# FubarinoMini_v14.net
KiCad netlist of a schematic drawn in EAGLE
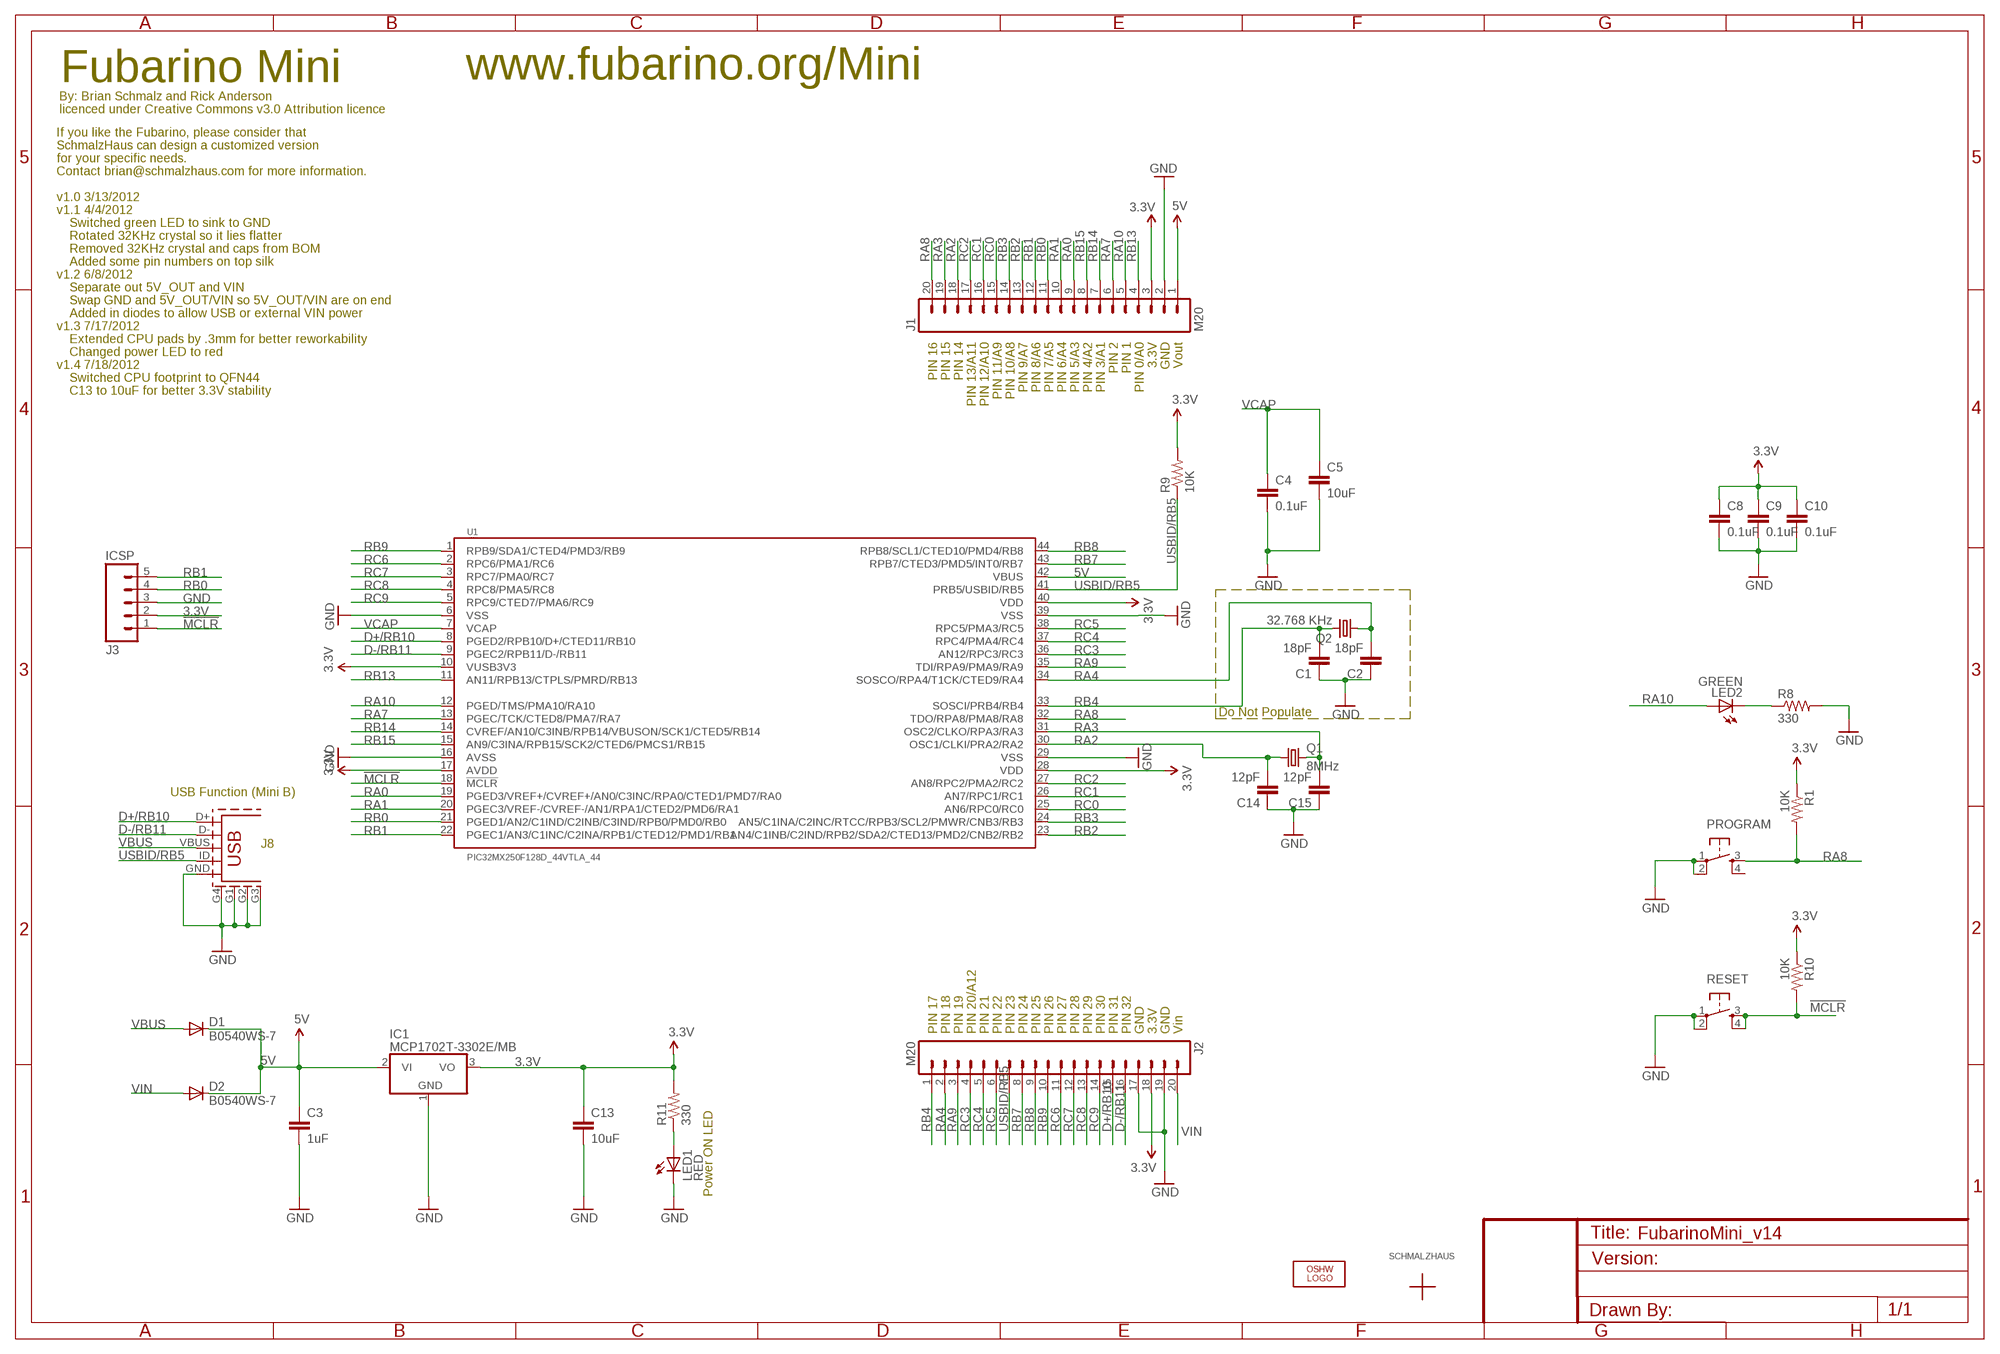
[diagram p0: schematic, sheet 1]

(export (version "E")
  (design (tool "Eeschema 10.0.6"))
  (components
    (comp (ref "C1")
      (value "18pF")
      (footprint "eagle-import:0603-CAP")
      (libsource (lib "eagle-import") (part "SparkFun_CAP0603-CAP"))
    )
    (comp (ref "C2")
      (value "18pF")
      (footprint "eagle-import:0603-CAP")
      (libsource (lib "eagle-import") (part "SparkFun_CAP0603-CAP"))
    )
    (comp (ref "C3")
      (value "1uF")
      (footprint "eagle-import:0603-CAP")
      (libsource (lib "eagle-import") (part "SparkFun_CAP0603-CAP"))
    )
    (comp (ref "C4")
      (value "0.1uF")
      (footprint "eagle-import:0603-CAP")
      (libsource (lib "eagle-import") (part "SparkFun_CAP0603-CAP"))
    )
    (comp (ref "C5")
      (value "10uF")
      (footprint "eagle-import:0805")
      (libsource (lib "eagle-import") (part "CAP0805"))
    )
    (comp (ref "C8")
      (value "0.1uF")
      (footprint "eagle-import:0603-CAP")
      (libsource (lib "eagle-import") (part "SparkFun_CAP0603-CAP"))
    )
    (comp (ref "C9")
      (value "0.1uF")
      (footprint "eagle-import:0603-CAP")
      (libsource (lib "eagle-import") (part "SparkFun_CAP0603-CAP"))
    )
    (comp (ref "C10")
      (value "0.1uF")
      (footprint "eagle-import:0603")
      (libsource (lib "eagle-import") (part "CAP0603"))
    )
    (comp (ref "C13")
      (value "10uF")
      (footprint "eagle-import:0805")
      (libsource (lib "eagle-import") (part "SparkFun02-20-08_CAP0805"))
    )
    (comp (ref "C14")
      (value "12pF")
      (footprint "eagle-import:0603-CAP")
      (libsource (lib "eagle-import") (part "SparkFun_CAP0603-CAP"))
    )
    (comp (ref "C15")
      (value "12pF")
      (footprint "eagle-import:0603-CAP")
      (libsource (lib "eagle-import") (part "SparkFun_CAP0603-CAP"))
    )
    (comp (ref "D1")
      (value "B0540WS-7")
      (footprint "eagle-import:SOD-323")
      (libsource (lib "eagle-import") (part "DIODESOD"))
    )
    (comp (ref "D2")
      (value "B0540WS-7")
      (footprint "eagle-import:SOD-323")
      (libsource (lib "eagle-import") (part "DIODESOD"))
    )
    (comp (ref "IC1")
      (value "MCP1702T-3302E/MB")
      (footprint "eagle-import:SOT89")
      (libsource (lib "eagle-import") (part "MCP1703MB33"))
    )
    (comp (ref "ICSP")
      (value "J3")
      (footprint "eagle-import:1X05_NOSILK")
      (libsource (lib "eagle-import") (part "M05NOSLILK"))
    )
    (comp (ref "J1")
      (value "M20")
      (footprint "eagle-import:1X20_NO_PIN1")
      (libsource (lib "eagle-import") (part "M20"))
    )
    (comp (ref "J2")
      (value "M20")
      (footprint "eagle-import:1X20_NO_PIN1")
      (libsource (lib "eagle-import") (part "M20"))
    )
    (comp (ref "J8")
      (value "USB_5PIN")
      (footprint "eagle-import:USB-MINIB")
      (libsource (lib "eagle-import") (part "USB_5PIN"))
    )
    (comp (ref "LED1")
      (value "RED")
      (footprint "eagle-import:LED-0603")
      (libsource (lib "eagle-import") (part "LED0603"))
    )
    (comp (ref "LED2")
      (value "GREEN")
      (footprint "eagle-import:LED-0603")
      (libsource (lib "eagle-import") (part "LED0603"))
    )
    (comp (ref "LOGO1")
      (value "OSHW_LOGO_8MILX0070-NT")
      (footprint "eagle-import:OSHW_8X70_NOTEXT")
      (libsource (lib "eagle-import") (part "OSHW_LOGO_8MILX0070-NT"))
    )
    (comp (ref "PROGRAM")
      (value "TAC_SWITCHSND")
      (footprint "eagle-import:TACTILE_SWITCH_SMD")
      (libsource (lib "eagle-import") (part "TAC_SWITCHSND"))
    )
    (comp (ref "Q1")
      (value "8MHz")
      (footprint "eagle-import:NX5032_5MM_3.2MM_CRYSTAL")
      (libsource (lib "eagle-import") (part "CRYSTALNX5032"))
    )
    (comp (ref "Q2")
      (value "32.768 KHz")
      (footprint "eagle-import:TC26H")
      (libsource (lib "eagle-import") (part "CRYSTALTC26H"))
    )
    (comp (ref "R1")
      (value "10K")
      (footprint "eagle-import:0603-RES")
      (libsource (lib "eagle-import") (part "RESISTOR0603-RES"))
    )
    (comp (ref "R8")
      (value "330")
      (footprint "eagle-import:0603-RES")
      (libsource (lib "eagle-import") (part "RESISTOR0603-RES"))
    )
    (comp (ref "R9")
      (value "10K")
      (footprint "eagle-import:0603-RES")
      (libsource (lib "eagle-import") (part "RESISTOR0603-RES"))
    )
    (comp (ref "R10")
      (value "10K")
      (footprint "eagle-import:0603-RES")
      (libsource (lib "eagle-import") (part "RESISTOR0603-RES"))
    )
    (comp (ref "R11")
      (value "330")
      (footprint "eagle-import:0603-RES")
      (libsource (lib "eagle-import") (part "RESISTOR0603-RES"))
    )
    (comp (ref "RESET")
      (value "TAC_SWITCHSND")
      (footprint "eagle-import:TACTILE_SWITCH_SMD")
      (libsource (lib "eagle-import") (part "TAC_SWITCHSND"))
    )
    (comp (ref "U$1")
      (value "SCHMALZHAUSSCHMALZHAUS_SMALL")
      (footprint "eagle-import:SCHMALZHAUS_SMALL")
      (libsource (lib "eagle-import") (part "SCHMALZHAUSSCHMALZHAUS_SMALL"))
    )
    (comp (ref "U1")
      (value "PIC32MX250F128D_44VTLA_44")
      (footprint "eagle-import:QFN-44-8X8-NOPAD")
      (libsource (lib "eagle-import") (part "PIC32MX2XX_44QFN44"))
    )
  )
  (nets
    (net (code "1") (name "/D+{slash}RB10") (class "Default")
      (node (ref "J2") (pin "15") (pinfunction "15_15") (pintype "passive"))
      (node (ref "J8") (pin "D+") (pinfunction "D+_D+") (pintype "bidirectional"))
      (node (ref "U1") (pin "8") (pinfunction "PGED2/RPB10/D+/CTED11/RB10_8") (pintype "bidirectional"))
    )
    (net (code "2") (name "/D-{slash}RB11") (class "Default")
      (node (ref "J2") (pin "16") (pinfunction "16_16") (pintype "passive"))
      (node (ref "J8") (pin "D-") (pinfunction "D-_D-") (pintype "bidirectional"))
      (node (ref "U1") (pin "9") (pinfunction "PGEC2/RPB11/D-/RB11_9") (pintype "bidirectional"))
    )
    (net (code "3") (name "/RA0") (class "Default")
      (node (ref "J1") (pin "9") (pinfunction "9_9") (pintype "passive"))
      (node (ref "U1") (pin "19") (pinfunction "PGED3/VREF+/CVREF+/AN0/C3INC/RPA0/CTED1/PMD7/RA0_19") (pintype "bidirectional"))
    )
    (net (code "4") (name "/RA1") (class "Default")
      (node (ref "J1") (pin "10") (pinfunction "10_10") (pintype "passive"))
      (node (ref "U1") (pin "20") (pinfunction "PGEC3/VREF-/CVREF-/AN1/RPA1/CTED2/PMD6/RA1_20") (pintype "bidirectional"))
    )
    (net (code "5") (name "/RA2") (class "Default")
      (node (ref "C14") (pin "2") (pinfunction "2_2") (pintype "passive"))
      (node (ref "J1") (pin "18") (pinfunction "18_18") (pintype "passive"))
      (node (ref "Q1") (pin "1") (pinfunction "1_1") (pintype "passive"))
      (node (ref "U1") (pin "30") (pinfunction "OSC1/CLKI/PRA2/RA2_30") (pintype "bidirectional"))
    )
    (net (code "6") (name "/RA3") (class "Default")
      (node (ref "C15") (pin "2") (pinfunction "2_2") (pintype "passive"))
      (node (ref "J1") (pin "19") (pinfunction "19_19") (pintype "passive"))
      (node (ref "Q1") (pin "2") (pinfunction "2_2") (pintype "passive"))
      (node (ref "U1") (pin "31") (pinfunction "OSC2/CLKO/RPA3/RA3_31") (pintype "bidirectional"))
    )
    (net (code "7") (name "/RA4") (class "Default")
      (node (ref "C2") (pin "2") (pinfunction "2_2") (pintype "passive"))
      (node (ref "J2") (pin "2") (pinfunction "2_2") (pintype "passive"))
      (node (ref "Q2") (pin "1") (pinfunction "1_1") (pintype "passive"))
      (node (ref "U1") (pin "34") (pinfunction "SOSCO/RPA4/T1CK/CTED9/RA4_34") (pintype "bidirectional"))
    )
    (net (code "8") (name "/RA7") (class "Default")
      (node (ref "J1") (pin "6") (pinfunction "6_6") (pintype "passive"))
      (node (ref "U1") (pin "13") (pinfunction "PGEC/TCK/CTED8/PMA7/RA7_13") (pintype "bidirectional"))
    )
    (net (code "9") (name "/RA8") (class "Default")
      (node (ref "J1") (pin "20") (pinfunction "20_20") (pintype "passive"))
      (node (ref "PROGRAM") (pin "3") (pinfunction "3_3") (pintype "passive"))
      (node (ref "R1") (pin "2") (pinfunction "2_2") (pintype "passive"))
      (node (ref "U1") (pin "32") (pinfunction "TDO/RPA8/PMA8/RA8_32") (pintype "bidirectional"))
    )
    (net (code "10") (name "/RA9") (class "Default")
      (node (ref "J2") (pin "3") (pinfunction "3_3") (pintype "passive"))
      (node (ref "U1") (pin "35") (pinfunction "TDI/RPA9/PMA9/RA9_35") (pintype "bidirectional"))
    )
    (net (code "11") (name "/RA10") (class "Default")
      (node (ref "J1") (pin "5") (pinfunction "5_5") (pintype "passive"))
      (node (ref "LED2") (pin "A") (pinfunction "A_A") (pintype "passive"))
      (node (ref "U1") (pin "12") (pinfunction "PGED/TMS/PMA10/RA10_12") (pintype "bidirectional"))
    )
    (net (code "12") (name "/RB0") (class "Default")
      (node (ref "ICSP") (pin "4") (pinfunction "4_4") (pintype "passive"))
      (node (ref "J1") (pin "11") (pinfunction "11_11") (pintype "passive"))
      (node (ref "U1") (pin "21") (pinfunction "PGED1/AN2/C1IND/C2INB/C3IND/RPB0/PMD0/RB0_21") (pintype "bidirectional"))
    )
    (net (code "13") (name "/RB1") (class "Default")
      (node (ref "ICSP") (pin "5") (pinfunction "5_5") (pintype "passive"))
      (node (ref "J1") (pin "12") (pinfunction "12_12") (pintype "passive"))
      (node (ref "U1") (pin "22") (pinfunction "PGEC1/AN3/C1INC/C2INA/RPB1/CTED12/PMD1/RB1_22") (pintype "bidirectional"))
    )
    (net (code "14") (name "/RB2") (class "Default")
      (node (ref "J1") (pin "13") (pinfunction "13_13") (pintype "passive"))
      (node (ref "U1") (pin "23") (pinfunction "AN4/C1INB/C2IND/RPB2/SDA2/CTED13/PMD2/CNB2/RB2_23") (pintype "bidirectional"))
    )
    (net (code "15") (name "/RB3") (class "Default")
      (node (ref "J1") (pin "14") (pinfunction "14_14") (pintype "passive"))
      (node (ref "U1") (pin "24") (pinfunction "AN5/C1INA/C2INC/RTCC/RPB3/SCL2/PMWR/CNB3/RB3_24") (pintype "bidirectional"))
    )
    (net (code "16") (name "/RB4") (class "Default")
      (node (ref "C1") (pin "2") (pinfunction "2_2") (pintype "passive"))
      (node (ref "J2") (pin "1") (pinfunction "1_1") (pintype "passive"))
      (node (ref "Q2") (pin "2") (pinfunction "2_2") (pintype "passive"))
      (node (ref "U1") (pin "33") (pinfunction "SOSCI/PRB4/RB4_33") (pintype "bidirectional"))
    )
    (net (code "17") (name "/RB7") (class "Default")
      (node (ref "J2") (pin "8") (pinfunction "8_8") (pintype "passive"))
      (node (ref "U1") (pin "43") (pinfunction "RPB7/CTED3/PMD5/INT0/RB7_43") (pintype "bidirectional"))
    )
    (net (code "18") (name "/RB8") (class "Default")
      (node (ref "J2") (pin "9") (pinfunction "9_9") (pintype "passive"))
      (node (ref "U1") (pin "44") (pinfunction "RPB8/SCL1/CTED10/PMD4/RB8_44") (pintype "bidirectional"))
    )
    (net (code "19") (name "/RB9") (class "Default")
      (node (ref "J2") (pin "10") (pinfunction "10_10") (pintype "passive"))
      (node (ref "U1") (pin "1") (pinfunction "RPB9/SDA1/CTED4/PMD3/RB9_1") (pintype "bidirectional"))
    )
    (net (code "20") (name "/RB13") (class "Default")
      (node (ref "J1") (pin "4") (pinfunction "4_4") (pintype "passive"))
      (node (ref "U1") (pin "11") (pinfunction "AN11/RPB13/CTPLS/PMRD/RB13_11") (pintype "bidirectional"))
    )
    (net (code "21") (name "/RB14") (class "Default")
      (node (ref "J1") (pin "7") (pinfunction "7_7") (pintype "passive"))
      (node (ref "U1") (pin "14") (pinfunction "CVREF/AN10/C3INB/RPB14/VBUSON/SCK1/CTED5/RB14_14") (pintype "bidirectional"))
    )
    (net (code "22") (name "/RB15") (class "Default")
      (node (ref "J1") (pin "8") (pinfunction "8_8") (pintype "passive"))
      (node (ref "U1") (pin "15") (pinfunction "AN9/C3INA/RPB15/SCK2/CTED6/PMCS1/RB15_15") (pintype "bidirectional"))
    )
    (net (code "23") (name "/RC0") (class "Default")
      (node (ref "J1") (pin "15") (pinfunction "15_15") (pintype "passive"))
      (node (ref "U1") (pin "25") (pinfunction "AN6/RPC0/RC0_25") (pintype "bidirectional"))
    )
    (net (code "24") (name "/RC1") (class "Default")
      (node (ref "J1") (pin "16") (pinfunction "16_16") (pintype "passive"))
      (node (ref "U1") (pin "26") (pinfunction "AN7/RPC1/RC1_26") (pintype "bidirectional"))
    )
    (net (code "25") (name "/RC2") (class "Default")
      (node (ref "J1") (pin "17") (pinfunction "17_17") (pintype "passive"))
      (node (ref "U1") (pin "27") (pinfunction "AN8/RPC2/PMA2/RC2_27") (pintype "bidirectional"))
    )
    (net (code "26") (name "/RC3") (class "Default")
      (node (ref "J2") (pin "4") (pinfunction "4_4") (pintype "passive"))
      (node (ref "U1") (pin "36") (pinfunction "AN12/RPC3/RC3_36") (pintype "bidirectional"))
    )
    (net (code "27") (name "/RC4") (class "Default")
      (node (ref "J2") (pin "5") (pinfunction "5_5") (pintype "passive"))
      (node (ref "U1") (pin "37") (pinfunction "RPC4/PMA4/RC4_37") (pintype "bidirectional"))
    )
    (net (code "28") (name "/RC5") (class "Default")
      (node (ref "J2") (pin "6") (pinfunction "6_6") (pintype "passive"))
      (node (ref "U1") (pin "38") (pinfunction "RPC5/PMA3/RC5_38") (pintype "bidirectional"))
    )
    (net (code "29") (name "/RC6") (class "Default")
      (node (ref "J2") (pin "11") (pinfunction "11_11") (pintype "passive"))
      (node (ref "U1") (pin "2") (pinfunction "RPC6/PMA1/RC6_2") (pintype "bidirectional"))
    )
    (net (code "30") (name "/RC7") (class "Default")
      (node (ref "J2") (pin "12") (pinfunction "12_12") (pintype "passive"))
      (node (ref "U1") (pin "3") (pinfunction "RPC7/PMA0/RC7_3") (pintype "bidirectional"))
    )
    (net (code "31") (name "/RC8") (class "Default")
      (node (ref "J2") (pin "13") (pinfunction "13_13") (pintype "passive"))
      (node (ref "U1") (pin "4") (pinfunction "RPC8/PMA5/RC8_4") (pintype "bidirectional"))
    )
    (net (code "32") (name "/RC9") (class "Default")
      (node (ref "J2") (pin "14") (pinfunction "14_14") (pintype "passive"))
      (node (ref "U1") (pin "5") (pinfunction "RPC9/CTED7/PMA6/RC9_5") (pintype "bidirectional"))
    )
    (net (code "33") (name "/USBID{slash}RB5") (class "Default")
      (node (ref "J2") (pin "7") (pinfunction "7_7") (pintype "passive"))
      (node (ref "J8") (pin "ID") (pinfunction "USB_ID_ID") (pintype "bidirectional"))
      (node (ref "R9") (pin "1") (pinfunction "1_1") (pintype "passive"))
      (node (ref "U1") (pin "41") (pinfunction "PRB5/USBID/RB5_41") (pintype "bidirectional"))
    )
    (net (code "34") (name "/VBUS") (class "Default")
      (node (ref "D1") (pin "2") (pinfunction "A_2") (pintype "passive"))
      (node (ref "J8") (pin "VBUS") (pinfunction "VBUS_VBUS") (pintype "bidirectional"))
    )
    (net (code "35") (name "/VCAP") (class "Default")
      (node (ref "C4") (pin "1") (pinfunction "1_1") (pintype "passive"))
      (node (ref "C5") (pin "1") (pinfunction "1_1") (pintype "passive"))
      (node (ref "U1") (pin "7") (pinfunction "VCAP_7") (pintype "bidirectional"))
    )
    (net (code "36") (name "/VIN") (class "Default")
      (node (ref "D2") (pin "2") (pinfunction "A_2") (pintype "passive"))
      (node (ref "J2") (pin "20") (pinfunction "20_20") (pintype "passive"))
    )
    (net (code "37") (name "/~{MCLR}") (class "Default")
      (node (ref "ICSP") (pin "1") (pinfunction "1_1") (pintype "passive"))
      (node (ref "R10") (pin "2") (pinfunction "2_2") (pintype "passive"))
      (node (ref "RESET") (pin "3") (pinfunction "3_3") (pintype "passive"))
      (node (ref "RESET") (pin "4") (pinfunction "4_4") (pintype "passive"))
      (node (ref "U1") (pin "18") (pinfunction "~{MCLR}_18") (pintype "bidirectional"))
    )
    (net (code "38") (name "3.3V") (class "Default")
      (node (ref "C10") (pin "1") (pinfunction "1_1") (pintype "passive"))
      (node (ref "C13") (pin "1") (pinfunction "1_1") (pintype "passive"))
      (node (ref "C8") (pin "1") (pinfunction "1_1") (pintype "passive"))
      (node (ref "C9") (pin "1") (pinfunction "1_1") (pintype "passive"))
      (node (ref "IC1") (pin "3") (pinfunction "VO_3") (pintype "passive"))
      (node (ref "ICSP") (pin "2") (pinfunction "2_2") (pintype "passive"))
      (node (ref "J1") (pin "3") (pinfunction "3_3") (pintype "passive"))
      (node (ref "J2") (pin "18") (pinfunction "18_18") (pintype "passive"))
      (node (ref "R1") (pin "1") (pinfunction "1_1") (pintype "passive"))
      (node (ref "R10") (pin "1") (pinfunction "1_1") (pintype "passive"))
      (node (ref "R11") (pin "2") (pinfunction "2_2") (pintype "passive"))
      (node (ref "R9") (pin "2") (pinfunction "2_2") (pintype "passive"))
      (node (ref "U1") (pin "10") (pinfunction "VUSB3V3_10") (pintype "bidirectional"))
      (node (ref "U1") (pin "17") (pinfunction "AVDD_17") (pintype "bidirectional"))
      (node (ref "U1") (pin "28") (pinfunction "VDD_28") (pintype "bidirectional"))
      (node (ref "U1") (pin "40") (pinfunction "VDD_40") (pintype "bidirectional"))
    )
    (net (code "39") (name "5V") (class "Default")
      (node (ref "C3") (pin "1") (pinfunction "1_1") (pintype "passive"))
      (node (ref "D1") (pin "1") (pinfunction "C_1") (pintype "passive"))
      (node (ref "D2") (pin "1") (pinfunction "C_1") (pintype "passive"))
      (node (ref "IC1") (pin "2") (pinfunction "VI_2") (pintype "input"))
      (node (ref "IC1") (pin "2@1") (pinfunction "VI1_2@1") (pintype "input"))
      (node (ref "J1") (pin "1") (pinfunction "1_1") (pintype "passive"))
      (node (ref "U1") (pin "42") (pinfunction "VBUS_42") (pintype "bidirectional"))
    )
    (net (code "40") (name "GND") (class "Default")
      (node (ref "C1") (pin "1") (pinfunction "1_1") (pintype "passive"))
      (node (ref "C10") (pin "2") (pinfunction "2_2") (pintype "passive"))
      (node (ref "C13") (pin "2") (pinfunction "2_2") (pintype "passive"))
      (node (ref "C14") (pin "1") (pinfunction "1_1") (pintype "passive"))
      (node (ref "C15") (pin "1") (pinfunction "1_1") (pintype "passive"))
      (node (ref "C2") (pin "1") (pinfunction "1_1") (pintype "passive"))
      (node (ref "C3") (pin "2") (pinfunction "2_2") (pintype "passive"))
      (node (ref "C4") (pin "2") (pinfunction "2_2") (pintype "passive"))
      (node (ref "C5") (pin "2") (pinfunction "2_2") (pintype "passive"))
      (node (ref "C8") (pin "2") (pinfunction "2_2") (pintype "passive"))
      (node (ref "C9") (pin "2") (pinfunction "2_2") (pintype "passive"))
      (node (ref "IC1") (pin "1") (pinfunction "GND_1") (pintype "passive"))
      (node (ref "ICSP") (pin "3") (pinfunction "3_3") (pintype "passive"))
      (node (ref "J1") (pin "2") (pinfunction "2_2") (pintype "passive"))
      (node (ref "J2") (pin "17") (pinfunction "17_17") (pintype "passive"))
      (node (ref "J2") (pin "19") (pinfunction "19_19") (pintype "passive"))
      (node (ref "J8") (pin "G1") (pinfunction "P$1_G1") (pintype "bidirectional"))
      (node (ref "J8") (pin "G2") (pinfunction "P$2_G2") (pintype "bidirectional"))
      (node (ref "J8") (pin "G3") (pinfunction "P$3_G3") (pintype "bidirectional"))
      (node (ref "J8") (pin "G4") (pinfunction "SHIELD_G4") (pintype "bidirectional"))
      (node (ref "J8") (pin "GND") (pinfunction "GND_GND") (pintype "bidirectional"))
      (node (ref "LED1") (pin "C") (pinfunction "C_C") (pintype "passive"))
      (node (ref "PROGRAM") (pin "1") (pinfunction "1_1") (pintype "passive"))
      (node (ref "PROGRAM") (pin "2") (pinfunction "2_2") (pintype "passive"))
      (node (ref "R8") (pin "2") (pinfunction "2_2") (pintype "passive"))
      (node (ref "RESET") (pin "1") (pinfunction "1_1") (pintype "passive"))
      (node (ref "RESET") (pin "2") (pinfunction "2_2") (pintype "passive"))
      (node (ref "U1") (pin "16") (pinfunction "AVSS_16") (pintype "bidirectional"))
      (node (ref "U1") (pin "29") (pinfunction "VSS_29") (pintype "bidirectional"))
      (node (ref "U1") (pin "39") (pinfunction "VSS_39") (pintype "bidirectional"))
      (node (ref "U1") (pin "6") (pinfunction "VSS_6") (pintype "bidirectional"))
    )
    (net (code "41") (name "Net-(LED1-PadA)") (class "Default")
      (node (ref "LED1") (pin "A") (pinfunction "A_A") (pintype "passive"))
      (node (ref "R11") (pin "1") (pinfunction "1_1") (pintype "passive"))
    )
    (net (code "42") (name "Net-(LED2-PadC)") (class "Default")
      (node (ref "LED2") (pin "C") (pinfunction "C_C") (pintype "passive"))
      (node (ref "R8") (pin "1") (pinfunction "1_1") (pintype "passive"))
    )
    (net (code "43") (name "unconnected-(PROGRAM-Pad4)") (class "Default")
      (node (ref "PROGRAM") (pin "4") (pinfunction "4_4") (pintype "passive"))
    )
  )
)
